# 2_IMD_Input_Stage.net
KiCad netlist of a schematic drawn in Altium Designer
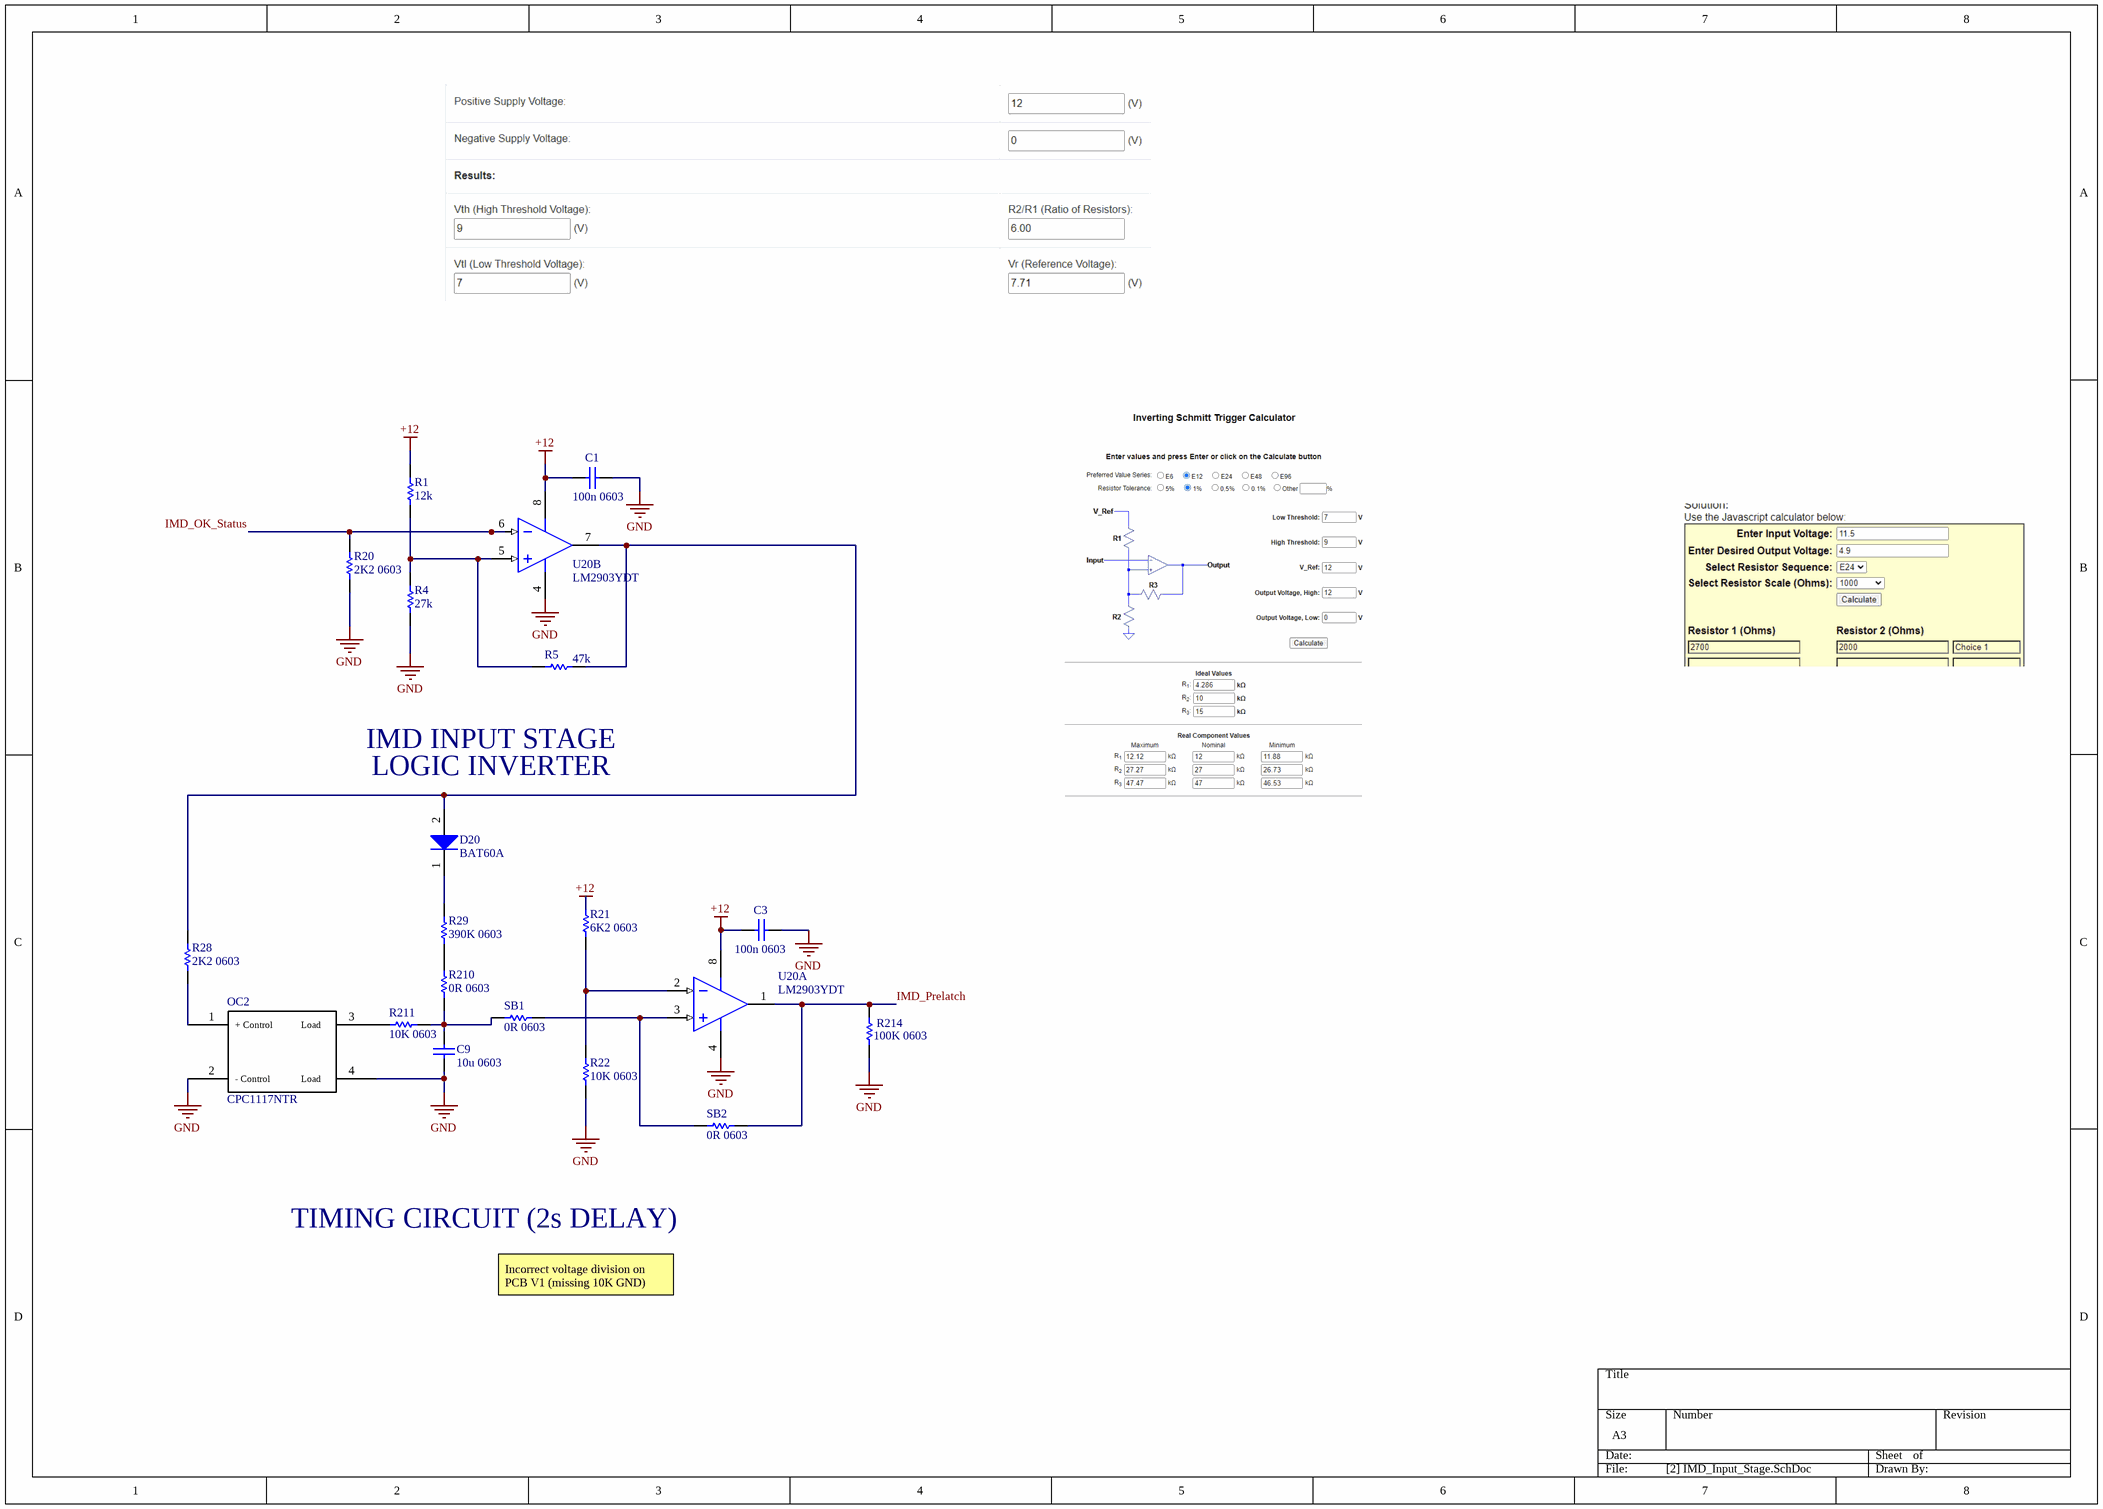
[diagram p0: [2] IMD_Input_Stage.SchDoc]

(export (version "E")
  (design (tool "Eeschema 10.0.6"))
  (components
    (comp (ref "C1")
      (value "100n 0603")
      (footprint "CAPC0603(1608)100_M")
      (description "Capacitor")
      (fields (field (name "PUBLISHER") "Altium Limited"))
      (libsource (lib "Miscellaneous Devices") (part "Cap"))
    )
    (comp (ref "C3")
      (value "100n 0603")
      (footprint "CAPC0603(1608)100_M")
      (description "Capacitor")
      (fields (field (name "PUBLISHER") "Altium Limited"))
      (libsource (lib "Miscellaneous Devices") (part "Cap"))
    )
    (comp (ref "C9")
      (value "10u 0603")
      (footprint "CAPC0603(1608)100_M")
      (description "Capacitor")
      (fields (field (name "PUBLISHER") "Altium Limited"))
      (libsource (lib "Miscellaneous Devices") (part "Cap"))
    )
    (comp (ref "D20")
      (value "BAT60A")
      (footprint "INF-SOD323_V")
      (description "Silicon Schottky Diode, -55 to 85 degC, SOD323, Reel, Green")
      (fields (field (name "MANUFACTURER") "Infineon"))
      (libsource (lib "Altium Content Vault") (part "INF-D_K1A2-2"))
    )
    (comp (ref "OC2")
      (value "CPC1117NTR")
      (footprint "SOP-4 (CPC1117NTR)")
      (libsource (lib "Schematic_Library_AMS_IMD") (part "CPC1117NTR"))
    )
    (comp (ref "R1")
      (value "12k")
      (footprint "RESC1608X55X25NL10T15")
      (description "Chip Resistor, 12 KOhm, +/- 1%, 100 mW, -55 to 155 degC, 0603 (1608 Metric), RoHS, Tape and Reel")
      (fields (field (name "TOLERANCE") "1%"))
      (libsource (lib "Altium Content Vault") (part "RES-2"))
    )
    (comp (ref "R4")
      (value "27k")
      (footprint "RESC1608X55X25LL10T15")
      (description "Chip Resistor, 27 KOhm, +/- 1%, 0.1 W, -55 to 155 degC, 0603 (1608 Metric), RoHS, Tape and Reel")
      (fields (field (name "MANUFACTURER") "Yageo") (field (name "TOLERANCE") "1%"))
      (libsource (lib "Altium Content Vault") (part "RES-2"))
    )
    (comp (ref "R5")
      (value "47k")
      (footprint "RESC1608X55X30NL15T15")
      (description "Chip Resistor, 47 KOhm, +/- 1%, 0.1 W, -55 to 155 degC, 0603 (1608 Metric), RoHS, Tape and Reel")
      (libsource (lib "Altium Content Vault") (part "RES-2"))
    )
    (comp (ref "R20")
      (value "2K2 0603")
      (footprint "CAPC0603(1608)100_M")
      (description "Resistor")
      (fields (field (name "PUBLISHER") "Altium Limited"))
      (libsource (lib "Miscellaneous Devices") (part "Res1"))
    )
    (comp (ref "R21")
      (value "6K2 0603")
      (footprint "CAPC0603(1608)100_M")
      (description "Resistor")
      (fields (field (name "PUBLISHER") "Altium Limited"))
      (libsource (lib "Miscellaneous Devices") (part "Res1"))
    )
    (comp (ref "R22")
      (value "10K 0603")
      (footprint "CAPC0603(1608)100_M")
      (description "Resistor")
      (fields (field (name "PUBLISHER") "Altium Limited"))
      (libsource (lib "Miscellaneous Devices") (part "Res1"))
    )
    (comp (ref "R28")
      (value "2K2 0603")
      (footprint "CAPC0603(1608)100_M")
      (description "Resistor")
      (fields (field (name "PUBLISHER") "Altium Limited"))
      (libsource (lib "Miscellaneous Devices") (part "Res1"))
    )
    (comp (ref "R29")
      (value "390K 0603")
      (footprint "CAPC0603(1608)100_M")
      (description "Resistor")
      (fields (field (name "PUBLISHER") "Altium Limited"))
      (libsource (lib "Miscellaneous Devices") (part "Res1"))
    )
    (comp (ref "R210")
      (value "0R 0603")
      (footprint "CAPC0603(1608)100_M")
      (description "Resistor")
      (fields (field (name "PUBLISHER") "Altium Limited"))
      (libsource (lib "Miscellaneous Devices") (part "Res1"))
    )
    (comp (ref "R211")
      (value "10K 0603")
      (footprint "CAPC0603(1608)100_M")
      (description "Resistor")
      (fields (field (name "PUBLISHER") "Altium Limited"))
      (libsource (lib "Miscellaneous Devices") (part "Res1"))
    )
    (comp (ref "R214")
      (value "100K 0603")
      (footprint "CAPC0603(1608)100_M")
      (description "Resistor")
      (fields (field (name "PUBLISHER") "Altium Limited"))
      (libsource (lib "Miscellaneous Devices") (part "Res1"))
    )
    (comp (ref "SB1")
      (value "0R 0603")
      (footprint "CAPC0603(1608)100_M")
      (description "Resistor")
      (fields (field (name "PUBLISHER") "Altium Limited"))
      (libsource (lib "Miscellaneous Devices") (part "Res1"))
    )
    (comp (ref "SB2")
      (value "0R 0603")
      (footprint "CAPC0603(1608)100_M")
      (description "Resistor")
      (fields (field (name "PUBLISHER") "Altium Limited"))
      (libsource (lib "Miscellaneous Devices") (part "Res1"))
    )
    (comp (ref "U20")
      (value "LM2903YDT")
      (footprint "ONSC-SOIC-8-751-07_V")
      (fields (field (name "MANUFACTURER") "On Semiconductor") (field (name "PARTNUMBER") "LM2903DR2G"))
      (libsource (lib "Altium Content Vault") (part "ONSC-LM2903X_X93_LMV393_NVC2903-8"))
    )
  )
  (nets
    (net (code "1") (name "+12") (class "Default")
      (node (ref "C1") (pin "1") (pinfunction "1_1") (pintype "passive"))
      (node (ref "C3") (pin "1") (pinfunction "1_1") (pintype "passive"))
      (node (ref "R1") (pin "1") (pinfunction "1_1") (pintype "passive"))
      (node (ref "R21") (pin "1") (pinfunction "1_1") (pintype "passive"))
      (node (ref "U20") (pin "8") (pinfunction "VCC_8") (pintype "power_in"))
    )
    (net (code "2") (name "/IMD_OK_Status") (class "Default")
      (node (ref "R20") (pin "1") (pinfunction "1_1") (pintype "passive"))
      (node (ref "U20") (pin "6") (pinfunction "INB-_6") (pintype "input"))
    )
    (net (code "3") (name "/IMD_Prelatch") (class "Default")
      (node (ref "R214") (pin "1") (pinfunction "1_1") (pintype "passive"))
      (node (ref "SB2") (pin "2") (pinfunction "2_2") (pintype "passive"))
      (node (ref "U20") (pin "1") (pinfunction "OUTA_1") (pintype "open_collector"))
    )
    (net (code "4") (name "GND") (class "Default")
      (node (ref "C1") (pin "2") (pinfunction "2_2") (pintype "passive"))
      (node (ref "C3") (pin "2") (pinfunction "2_2") (pintype "passive"))
      (node (ref "C9") (pin "2") (pinfunction "2_2") (pintype "passive"))
      (node (ref "OC2") (pin "2") (pinfunction "2_2") (pintype "passive"))
      (node (ref "OC2") (pin "4") (pinfunction "4_4") (pintype "passive"))
      (node (ref "R20") (pin "2") (pinfunction "2_2") (pintype "passive"))
      (node (ref "R214") (pin "2") (pinfunction "2_2") (pintype "passive"))
      (node (ref "R22") (pin "2") (pinfunction "2_2") (pintype "passive"))
      (node (ref "R4") (pin "1") (pinfunction "1_1") (pintype "passive"))
      (node (ref "U20") (pin "4") (pinfunction "GND_4") (pintype "power_in"))
    )
    (net (code "5") (name "Net-(C9-Pad1)") (class "Default")
      (node (ref "C9") (pin "1") (pinfunction "1_1") (pintype "passive"))
      (node (ref "R210") (pin "2") (pinfunction "2_2") (pintype "passive"))
      (node (ref "R211") (pin "2") (pinfunction "2_2") (pintype "passive"))
      (node (ref "SB1") (pin "1") (pinfunction "1_1") (pintype "passive"))
    )
    (net (code "6") (name "Net-(D20-A)") (class "Default")
      (node (ref "D20") (pin "2") (pinfunction "A_2") (pintype "passive"))
      (node (ref "R28") (pin "1") (pinfunction "1_1") (pintype "passive"))
      (node (ref "R5") (pin "2") (pinfunction "2_2") (pintype "passive"))
      (node (ref "U20") (pin "7") (pinfunction "OUTB_7") (pintype "open_collector"))
    )
    (net (code "7") (name "Net-(D20-K)") (class "Default")
      (node (ref "D20") (pin "1") (pinfunction "K_1") (pintype "passive"))
      (node (ref "R29") (pin "1") (pinfunction "1_1") (pintype "passive"))
    )
    (net (code "8") (name "Net-(OC2-Pad1)") (class "Default")
      (node (ref "OC2") (pin "1") (pinfunction "1_1") (pintype "passive"))
      (node (ref "R28") (pin "2") (pinfunction "2_2") (pintype "passive"))
    )
    (net (code "9") (name "Net-(OC2-Pad3)") (class "Default")
      (node (ref "OC2") (pin "3") (pinfunction "3_3") (pintype "passive"))
      (node (ref "R211") (pin "1") (pinfunction "1_1") (pintype "passive"))
    )
    (net (code "10") (name "Net-(R210-Pad1)") (class "Default")
      (node (ref "R210") (pin "1") (pinfunction "1_1") (pintype "passive"))
      (node (ref "R29") (pin "2") (pinfunction "2_2") (pintype "passive"))
    )
    (net (code "11") (name "Net-(U20A-INA+)") (class "Default")
      (node (ref "SB1") (pin "2") (pinfunction "2_2") (pintype "passive"))
      (node (ref "SB2") (pin "1") (pinfunction "1_1") (pintype "passive"))
      (node (ref "U20") (pin "3") (pinfunction "INA+_3") (pintype "input"))
    )
    (net (code "12") (name "Net-(U20A-INA-)") (class "Default")
      (node (ref "R21") (pin "2") (pinfunction "2_2") (pintype "passive"))
      (node (ref "R22") (pin "1") (pinfunction "1_1") (pintype "passive"))
      (node (ref "U20") (pin "2") (pinfunction "INA-_2") (pintype "input"))
    )
    (net (code "13") (name "Net-(U20B-INB+)") (class "Default")
      (node (ref "R1") (pin "2") (pinfunction "2_2") (pintype "passive"))
      (node (ref "R4") (pin "2") (pinfunction "2_2") (pintype "passive"))
      (node (ref "R5") (pin "1") (pinfunction "1_1") (pintype "passive"))
      (node (ref "U20") (pin "5") (pinfunction "INB+_5") (pintype "input"))
    )
  )
)
